# pwmdisplay.net
KiCad netlist of a schematic drawn in Altium Designer
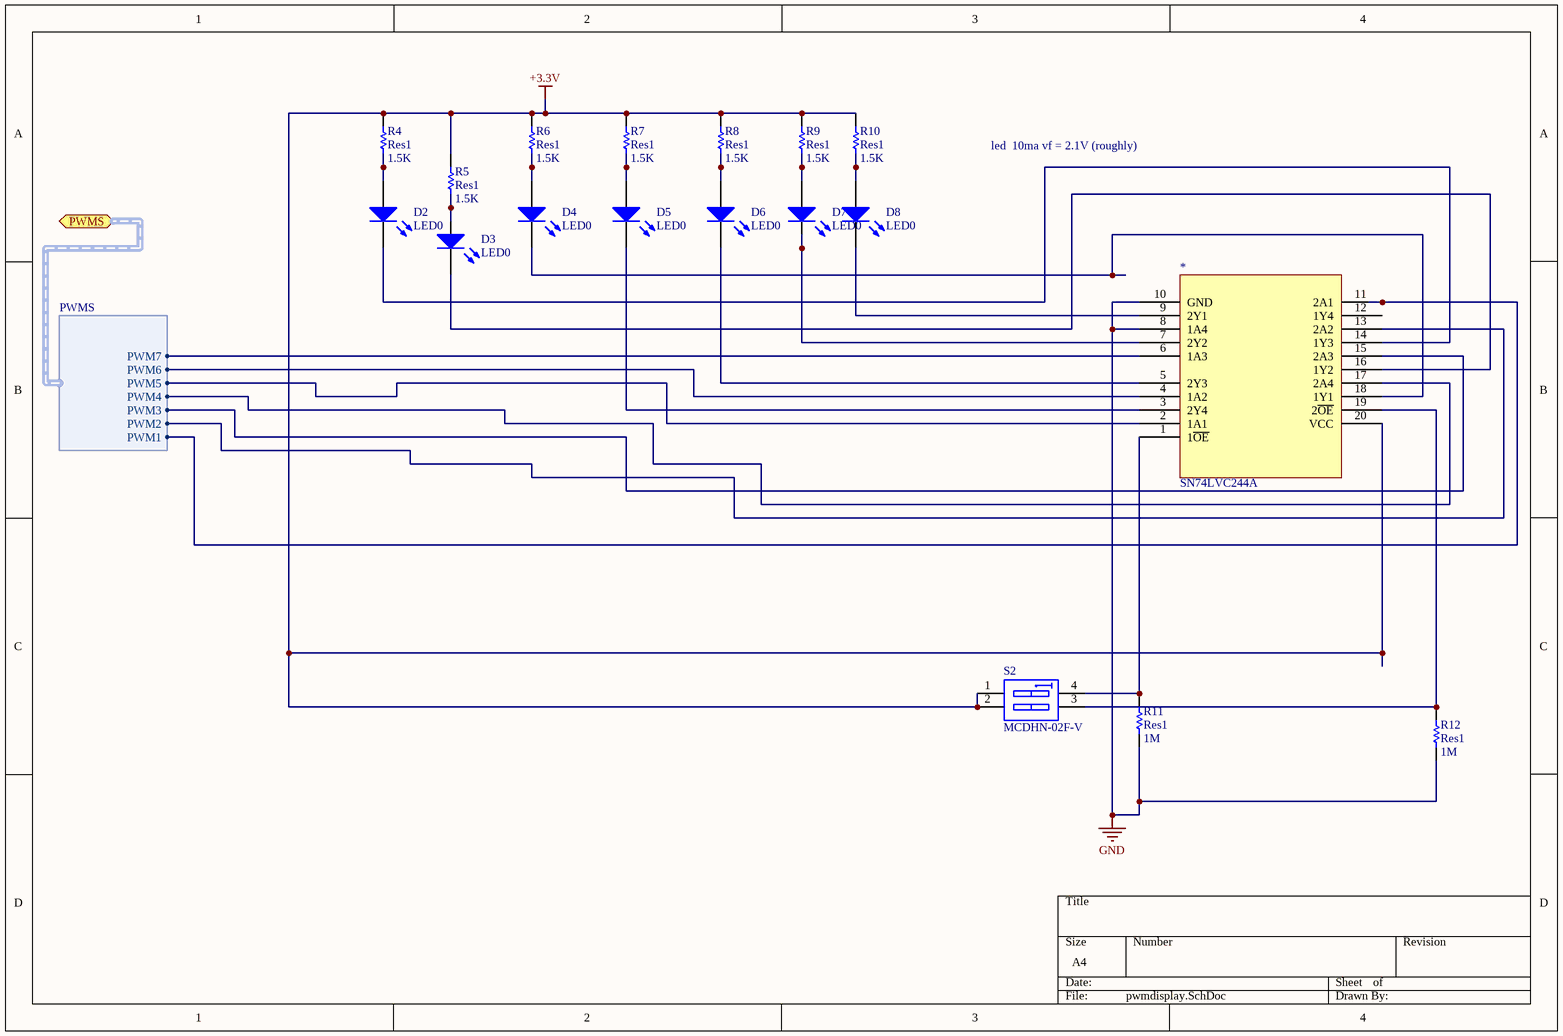
[diagram p0: pwmdisplay.SchDoc]

(export (version "E")
  (design (tool "Eeschema 10.0.6"))
  (components
    (comp (ref "*")
      (value "SN74LVC244A")
      (footprint "DW (R-PDS0-G20)")
      (libsource (lib "SN74LVC244A") (part "SN74LVC244A"))
    )
    (comp (ref "D2")
      (value "LED0")
      (footprint "LGQ971")
      (description "Typical INFRARED GaAs LED")
      (fields (field (name "PUBLISHER") "Altium Limited"))
      (libsource (lib "Miscellaneous Devices") (part "LED0"))
    )
    (comp (ref "D3")
      (value "LED0")
      (footprint "LGQ971:LGQ971")
      (description "Typical INFRARED GaAs LED")
      (fields (field (name "PUBLISHER") "Altium Limited"))
      (libsource (lib "Miscellaneous Devices") (part "LED0"))
    )
    (comp (ref "D4")
      (value "LED0")
      (footprint "LGQ971")
      (description "Typical INFRARED GaAs LED")
      (fields (field (name "PUBLISHER") "Altium Limited"))
      (libsource (lib "Miscellaneous Devices") (part "LED0"))
    )
    (comp (ref "D5")
      (value "LED0")
      (footprint "LGQ971")
      (description "Typical INFRARED GaAs LED")
      (fields (field (name "PUBLISHER") "Altium Limited"))
      (libsource (lib "Miscellaneous Devices") (part "LED0"))
    )
    (comp (ref "D6")
      (value "LED0")
      (footprint "LGQ971")
      (description "Typical INFRARED GaAs LED")
      (fields (field (name "PUBLISHER") "Altium Limited"))
      (libsource (lib "Miscellaneous Devices") (part "LED0"))
    )
    (comp (ref "D7")
      (value "LED0")
      (footprint "LGQ971")
      (description "Typical INFRARED GaAs LED")
      (fields (field (name "PUBLISHER") "Altium Limited"))
      (libsource (lib "Miscellaneous Devices") (part "LED0"))
    )
    (comp (ref "D8")
      (value "LED0")
      (footprint "LGQ971")
      (description "Typical INFRARED GaAs LED")
      (fields (field (name "PUBLISHER") "Altium Limited"))
      (libsource (lib "Miscellaneous Devices") (part "LED0"))
    )
    (comp (ref "R4")
      (value "Res1")
      (footprint "AXIAL-0.3")
      (description "Resistor")
      (fields (field (name "ALTIUM_VALUE") "1.5K") (field (name "PUBLISHER") "Altium Limited"))
      (libsource (lib "Miscellaneous Devices") (part "Res1"))
    )
    (comp (ref "R5")
      (value "Res1")
      (footprint "AXIAL-0.3")
      (description "Resistor")
      (fields (field (name "ALTIUM_VALUE") "1.5K") (field (name "PUBLISHER") "Altium Limited"))
      (libsource (lib "Miscellaneous Devices") (part "Res1"))
    )
    (comp (ref "R6")
      (value "Res1")
      (footprint "AXIAL-0.3")
      (description "Resistor")
      (fields (field (name "ALTIUM_VALUE") "1.5K") (field (name "PUBLISHER") "Altium Limited"))
      (libsource (lib "Miscellaneous Devices") (part "Res1"))
    )
    (comp (ref "R7")
      (value "Res1")
      (footprint "AXIAL-0.3")
      (description "Resistor")
      (fields (field (name "ALTIUM_VALUE") "1.5K") (field (name "PUBLISHER") "Altium Limited"))
      (libsource (lib "Miscellaneous Devices") (part "Res1"))
    )
    (comp (ref "R8")
      (value "Res1")
      (footprint "AXIAL-0.3")
      (description "Resistor")
      (fields (field (name "ALTIUM_VALUE") "1.5K") (field (name "PUBLISHER") "Altium Limited"))
      (libsource (lib "Miscellaneous Devices") (part "Res1"))
    )
    (comp (ref "R9")
      (value "Res1")
      (footprint "AXIAL-0.3")
      (description "Resistor")
      (fields (field (name "ALTIUM_VALUE") "1.5K") (field (name "PUBLISHER") "Altium Limited"))
      (libsource (lib "Miscellaneous Devices") (part "Res1"))
    )
    (comp (ref "R10")
      (value "Res1")
      (footprint "AXIAL-0.3")
      (description "Resistor")
      (fields (field (name "ALTIUM_VALUE") "1.5K") (field (name "PUBLISHER") "Altium Limited"))
      (libsource (lib "Miscellaneous Devices") (part "Res1"))
    )
    (comp (ref "R11")
      (value "Res1")
      (footprint "AXIAL-0.3")
      (description "Resistor")
      (fields (field (name "ALTIUM_VALUE") "1M") (field (name "PUBLISHER") "Altium Limited"))
      (libsource (lib "Miscellaneous Devices") (part "Res1"))
    )
    (comp (ref "R12")
      (value "Res1")
      (footprint "AXIAL-0.3")
      (description "Resistor")
      (fields (field (name "ALTIUM_VALUE") "1M") (field (name "PUBLISHER") "Altium Limited"))
      (libsource (lib "Miscellaneous Devices") (part "Res1"))
    )
    (comp (ref "S2")
      (value "MCDHN-02F-V")
      (footprint "MCDHN-02F-V")
      (description "DIP Switch, 2 Position, SPST")
      (fields (field (name "PUBLISHER") "Altium Limited"))
      (libsource (lib "Miscellaneous Devices") (part "SW DIP-2"))
    )
  )
  (nets
    (net (code "2") (name "+3.3V") (class "Default")
      (node (ref "*") (pin "20") (pinfunction "VCC_20") (pintype "passive"))
      (node (ref "R10") (pin "2") (pinfunction "2_2") (pintype "passive"))
      (node (ref "R4") (pin "2") (pinfunction "2_2") (pintype "passive"))
      (node (ref "R5") (pin "2") (pinfunction "2_2") (pintype "passive"))
      (node (ref "R6") (pin "2") (pinfunction "2_2") (pintype "passive"))
      (node (ref "R7") (pin "2") (pinfunction "2_2") (pintype "passive"))
      (node (ref "R8") (pin "2") (pinfunction "2_2") (pintype "passive"))
      (node (ref "R9") (pin "2") (pinfunction "2_2") (pintype "passive"))
      (node (ref "S2") (pin "1") (pinfunction "A1_1") (pintype "passive"))
      (node (ref "S2") (pin "2") (pinfunction "A2_2") (pintype "passive"))
    )
    (net (code "3") (name "/PWM1") (class "Default")
      (node (ref "*") (pin "11") (pinfunction "2A1_11") (pintype "passive"))
    )
    (net (code "4") (name "/PWM2") (class "Default")
      (node (ref "*") (pin "13") (pinfunction "2A2_13") (pintype "passive"))
    )
    (net (code "5") (name "/PWM3") (class "Default")
      (node (ref "*") (pin "15") (pinfunction "2A3_15") (pintype "passive"))
    )
    (net (code "6") (name "/PWM4") (class "Default")
      (node (ref "*") (pin "17") (pinfunction "2A4_17") (pintype "passive"))
    )
    (net (code "7") (name "/PWM5") (class "Default")
      (node (ref "*") (pin "2") (pinfunction "1A1_2") (pintype "passive"))
    )
    (net (code "8") (name "/PWM6") (class "Default")
      (node (ref "*") (pin "4") (pinfunction "1A2_4") (pintype "passive"))
    )
    (net (code "9") (name "/PWM7") (class "Default")
      (node (ref "*") (pin "6") (pinfunction "1A3_6") (pintype "passive"))
    )
    (net (code "11") (name "GND") (class "Default")
      (node (ref "*") (pin "10") (pinfunction "GND_10") (pintype "passive"))
      (node (ref "*") (pin "8") (pinfunction "1A4_8") (pintype "passive"))
      (node (ref "R11") (pin "1") (pinfunction "1_1") (pintype "passive"))
      (node (ref "R12") (pin "1") (pinfunction "1_1") (pintype "passive"))
    )
    (net (code "12") (name "Net-(*-1Y1)") (class "Default")
      (node (ref "*") (pin "18") (pinfunction "1Y1_18") (pintype "passive"))
      (node (ref "D4") (pin "2") (pinfunction "K_2") (pintype "passive"))
    )
    (net (code "13") (name "Net-(*-1Y2)") (class "Default")
      (node (ref "*") (pin "16") (pinfunction "1Y2_16") (pintype "passive"))
      (node (ref "D3") (pin "2") (pinfunction "K_2") (pintype "passive"))
    )
    (net (code "14") (name "Net-(*-1Y3)") (class "Default")
      (node (ref "*") (pin "14") (pinfunction "1Y3_14") (pintype "passive"))
      (node (ref "D2") (pin "2") (pinfunction "K_2") (pintype "passive"))
    )
    (net (code "15") (name "Net-(*-1~{OE})") (class "Default")
      (node (ref "*") (pin "1") (pinfunction "1~{OE}_1") (pintype "passive"))
      (node (ref "R11") (pin "2") (pinfunction "2_2") (pintype "passive"))
      (node (ref "S2") (pin "4") (pinfunction "B1_4") (pintype "passive"))
    )
    (net (code "16") (name "Net-(*-2Y1)") (class "Default")
      (node (ref "*") (pin "9") (pinfunction "2Y1_9") (pintype "passive"))
      (node (ref "D8") (pin "2") (pinfunction "K_2") (pintype "passive"))
    )
    (net (code "17") (name "Net-(*-2Y2)") (class "Default")
      (node (ref "*") (pin "7") (pinfunction "2Y2_7") (pintype "passive"))
      (node (ref "D7") (pin "2") (pinfunction "K_2") (pintype "passive"))
    )
    (net (code "18") (name "Net-(*-2Y3)") (class "Default")
      (node (ref "*") (pin "5") (pinfunction "2Y3_5") (pintype "passive"))
      (node (ref "D6") (pin "2") (pinfunction "K_2") (pintype "passive"))
    )
    (net (code "19") (name "Net-(*-2Y4)") (class "Default")
      (node (ref "*") (pin "3") (pinfunction "2Y4_3") (pintype "passive"))
      (node (ref "D5") (pin "2") (pinfunction "K_2") (pintype "passive"))
    )
    (net (code "20") (name "Net-(*-2~{OE})") (class "Default")
      (node (ref "*") (pin "19") (pinfunction "2~{OE}_19") (pintype "passive"))
      (node (ref "R12") (pin "2") (pinfunction "2_2") (pintype "passive"))
      (node (ref "S2") (pin "3") (pinfunction "B2_3") (pintype "passive"))
    )
    (net (code "21") (name "Net-(D2-A)") (class "Default")
      (node (ref "D2") (pin "1") (pinfunction "A_1") (pintype "passive"))
      (node (ref "R4") (pin "1") (pinfunction "1_1") (pintype "passive"))
    )
    (net (code "22") (name "Net-(D3-A)") (class "Default")
      (node (ref "D3") (pin "1") (pinfunction "A_1") (pintype "passive"))
      (node (ref "R5") (pin "1") (pinfunction "1_1") (pintype "passive"))
    )
    (net (code "23") (name "Net-(D4-A)") (class "Default")
      (node (ref "D4") (pin "1") (pinfunction "A_1") (pintype "passive"))
      (node (ref "R6") (pin "1") (pinfunction "1_1") (pintype "passive"))
    )
    (net (code "24") (name "Net-(D5-A)") (class "Default")
      (node (ref "D5") (pin "1") (pinfunction "A_1") (pintype "passive"))
      (node (ref "R7") (pin "1") (pinfunction "1_1") (pintype "passive"))
    )
    (net (code "25") (name "Net-(D6-A)") (class "Default")
      (node (ref "D6") (pin "1") (pinfunction "A_1") (pintype "passive"))
      (node (ref "R8") (pin "1") (pinfunction "1_1") (pintype "passive"))
    )
    (net (code "26") (name "Net-(D7-A)") (class "Default")
      (node (ref "D7") (pin "1") (pinfunction "A_1") (pintype "passive"))
      (node (ref "R9") (pin "1") (pinfunction "1_1") (pintype "passive"))
    )
    (net (code "27") (name "Net-(D8-A)") (class "Default")
      (node (ref "D8") (pin "1") (pinfunction "A_1") (pintype "passive"))
      (node (ref "R10") (pin "1") (pinfunction "1_1") (pintype "passive"))
    )
    (net (code "28") (name "unconnected-(*-1Y4-Pad12)") (class "Default")
      (node (ref "*") (pin "12") (pinfunction "1Y4_12") (pintype "passive"))
    )
  )
)
